# Power.net
KiCad netlist of a schematic drawn in Altium Designer
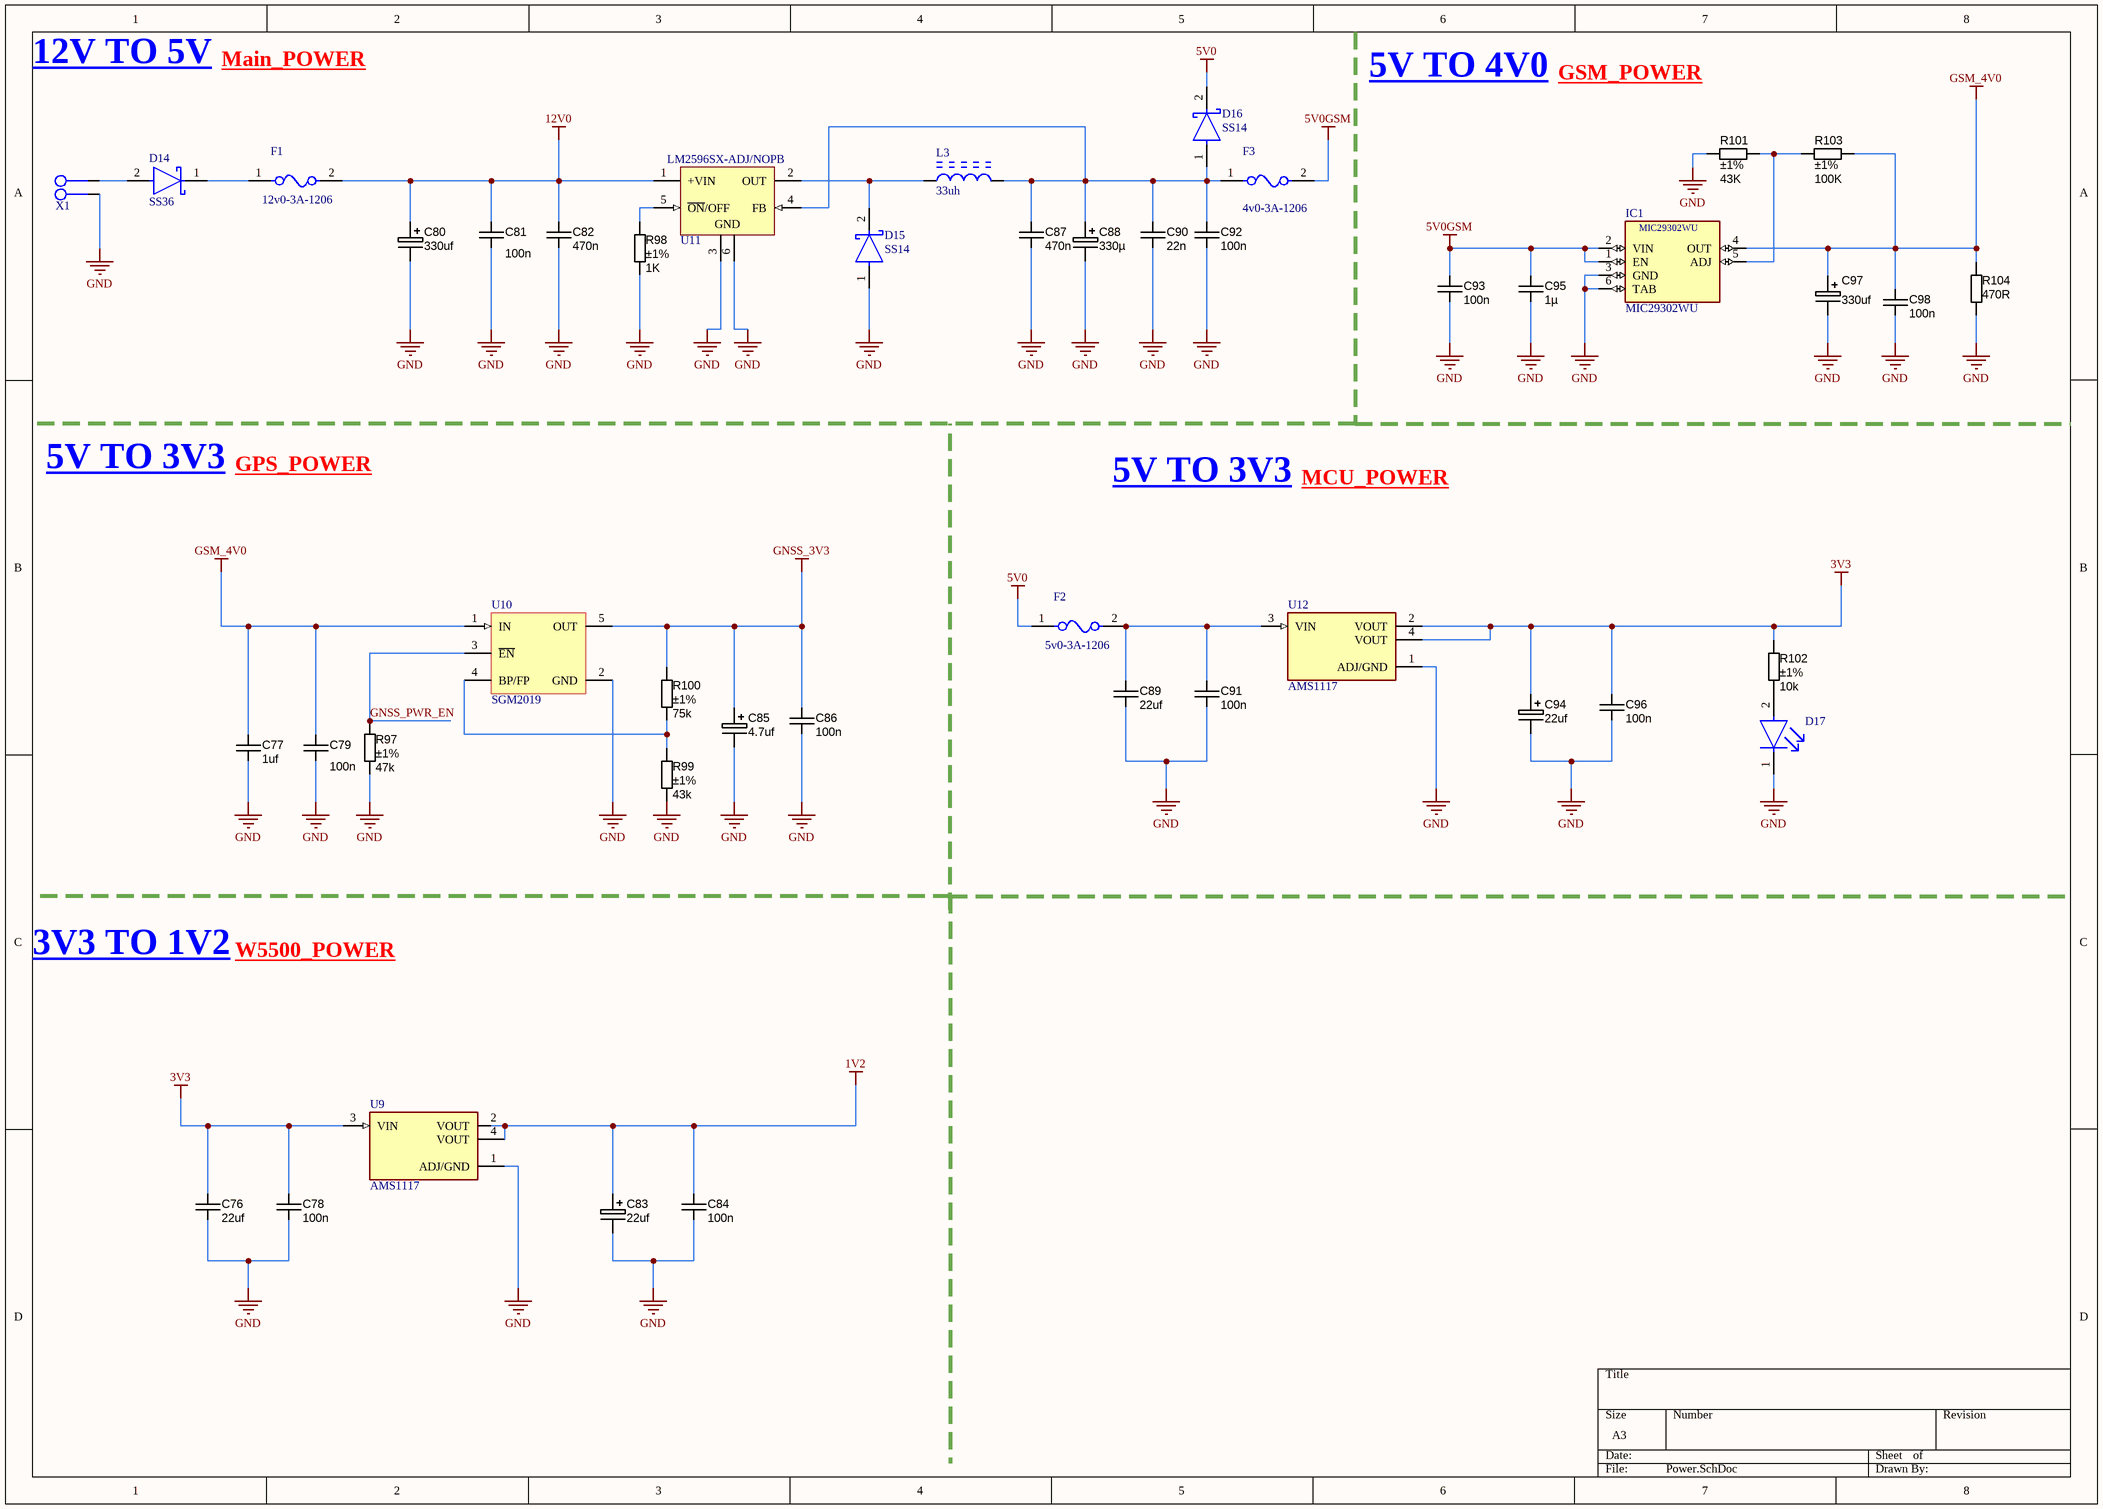
[diagram p0: Power.SchDoc]

(export (version "E")
  (design (tool "Eeschema 10.0.6"))
  (components
    (comp (ref "C76")
      (value "22uf")
      (footprint "CAPC1608X90N")
      (description "Capacitor SMD Cer 22uf 10% 16V X7R 0603")
      (fields (field (name "TOLERANCE") "±10%"))
      (libsource (lib "PBL - Capacitors") (part "CAPC_470n_0603_X7R_16V_10%"))
    )
    (comp (ref "C77")
      (value "1uf")
      (footprint "CAPC1608X90N")
      (description "Capacitor SMD Cer 1uf 10% 16V X7R 0603")
      (fields (field (name "TOLERANCE") "±10%"))
      (libsource (lib "PBL - Capacitors") (part "CAPC_470n_0603_X7R_16V_10%"))
    )
    (comp (ref "C78")
      (value "100n")
      (footprint "CAPC1608X90N")
      (description "Capacitor SMD Cer 100nF 10% 50V X7R 0603")
      (fields (field (name "TOLERANCE") "±10%") (field (name "Comment") "approved sub OK"))
      (libsource (lib "PBL - Capacitors") (part "CAPC_100n_0603_X7R_50V_10%"))
    )
    (comp (ref "C79")
      (value "100n")
      (footprint "CAPC1608X90N")
      (description "Capacitor SMD Cer 100nF 10% 16V X7R 0603")
      (fields (field (name "TOLERANCE") "±10%"))
      (libsource (lib "PBL - Capacitors") (part "CAPC_470n_0603_X7R_16V_10%"))
    )
    (comp (ref "C80")
      (value "330uf")
      (footprint "C_EL_8")
      (description "Capacitor SMD Tant 330uF 20% 6V3 2917")
      (fields
        (field (name "TOLERANCE") "±20%")
        (field (name "MANUFACTURER PART NUMBER") "T520D337M006ATE015")
      )
      (libsource (lib "PBL - Capacitors") (part "CAPT_330u_2917_6V3"))
    )
    (comp (ref "C81")
      (value "100n")
      (footprint "CAPC1608X90N")
      (description "Capacitor SMD Cer 100nF 10% 16V X7R 0603")
      (fields (field (name "TOLERANCE") "±10%"))
      (libsource (lib "PBL - Capacitors") (part "CAPC_470n_0603_X7R_16V_10%"))
    )
    (comp (ref "C82")
      (value "470n")
      (footprint "CAPC3216X180N")
      (description "Capacitor SMD Cer 470nF 10% 10V X5R 1206")
      (fields (field (name "TOLERANCE") "±10%") (field (name "Comment") "approved sub OK"))
      (libsource (lib "PBL - Capacitors") (part "CAPC_10u_1206_10V"))
    )
    (comp (ref "C83")
      (value "22uf")
      (footprint "C_TN_3216")
      (description "Capacitor SMD Tant 22uF 20% 6V3 2917")
      (fields
        (field (name "TOLERANCE") "±20%")
        (field (name "MANUFACTURER PART NUMBER") "T520D337M006ATE015")
      )
      (libsource (lib "PBL - Capacitors") (part "CAPT_330u_2917_6V3"))
    )
    (comp (ref "C84")
      (value "100n")
      (footprint "CAPC1608X90N")
      (description "Capacitor SMD Cer 100nF 10% 50V X7R 0603")
      (fields (field (name "TOLERANCE") "±10%") (field (name "Comment") "approved sub OK"))
      (libsource (lib "PBL - Capacitors") (part "CAPC_100n_0603_X7R_50V_10%"))
    )
    (comp (ref "C85")
      (value "4.7uf")
      (footprint "C_TN_3216")
      (description "Capacitor SMD Tant 4.7uF 20% 6V3 2917")
      (fields
        (field (name "TOLERANCE") "±20%")
        (field (name "MANUFACTURER PART NUMBER") "T520D337M006ATE015")
      )
      (libsource (lib "PBL - Capacitors") (part "CAPT_330u_2917_6V3"))
    )
    (comp (ref "C86")
      (value "100n")
      (footprint "CAPC1608X90N")
      (description "Capacitor SMD Cer 100nF 10% 50V X7R 0603")
      (fields (field (name "TOLERANCE") "±10%") (field (name "Comment") "approved sub OK"))
      (libsource (lib "PBL - Capacitors") (part "CAPC_100n_0603_X7R_50V_10%"))
    )
    (comp (ref "C87")
      (value "470n")
      (footprint "CAPC3216X180N")
      (description "Capacitor SMD Cer 470nF 10% 10V X5R 1206")
      (fields (field (name "TOLERANCE") "±10%") (field (name "Comment") "approved sub OK"))
      (libsource (lib "PBL - Capacitors") (part "CAPC_10u_1206_10V"))
    )
    (comp (ref "C88")
      (value "330µ")
      (footprint "C_TN_7343")
      (description "Capacitor SMD Tant 330uF 20% 6V3 2917")
      (fields
        (field (name "TOLERANCE") "±20%")
        (field (name "MANUFACTURER PART NUMBER") "T520D337M006ATE015")
      )
      (libsource (lib "PBL - Capacitors") (part "CAPT_330u_2917_6V3"))
    )
    (comp (ref "C89")
      (value "22uf")
      (footprint "CAPC1608X90N")
      (description "Capacitor SMD Cer 22uf 10% 16V X7R 0603")
      (fields (field (name "TOLERANCE") "±10%"))
      (libsource (lib "PBL - Capacitors") (part "CAPC_470n_0603_X7R_16V_10%"))
    )
    (comp (ref "C90")
      (value "22n")
      (footprint "CAPC1608X90N")
      (description "Capacitor SMD Cer 22nF 10% 16V X7R 0603")
      (fields (field (name "TOLERANCE") "±10%"))
      (libsource (lib "PBL - Capacitors") (part "CAPC_470n_0603_X7R_16V_10%"))
    )
    (comp (ref "C91")
      (value "100n")
      (footprint "CAPC1608X90N")
      (description "Capacitor SMD Cer 100nF 10% 50V X7R 0603")
      (fields (field (name "TOLERANCE") "±10%") (field (name "Comment") "approved sub OK"))
      (libsource (lib "PBL - Capacitors") (part "CAPC_100n_0603_X7R_50V_10%"))
    )
    (comp (ref "C92")
      (value "100n")
      (footprint "CAPC1608X90N")
      (description "Capacitor SMD Cer 100nF 10% 16V X7R 0603")
      (fields (field (name "TOLERANCE") "±10%"))
      (libsource (lib "PBL - Capacitors") (part "CAPC_470n_0603_X7R_16V_10%"))
    )
    (comp (ref "C93")
      (value "100n")
      (footprint "CAPC1608X90N")
      (description "Capacitor SMD Cer 100nF 10% 50V X7R 0603")
      (fields (field (name "TOLERANCE") "±10%") (field (name "Comment") "approved sub OK"))
      (libsource (lib "PBL - Capacitors") (part "CAPC_100n_0603_X7R_50V_10%"))
    )
    (comp (ref "C94")
      (value "22uf")
      (footprint "C_TN_3216")
      (description "Capacitor SMD Tant 22uF 20% 6V3 2917")
      (fields
        (field (name "TOLERANCE") "±20%")
        (field (name "MANUFACTURER PART NUMBER") "T520D337M006ATE015")
      )
      (libsource (lib "PBL - Capacitors") (part "CAPT_330u_2917_6V3"))
    )
    (comp (ref "C95")
      (value "1µ")
      (footprint "CAPC3216X180N")
      (description "Capacitor SMD Cer 1uF 10% 10V X5R 1206")
      (fields (field (name "TOLERANCE") "±10%") (field (name "Comment") "approved sub OK"))
      (libsource (lib "PBL - Capacitors") (part "CAPC_10u_1206_10V"))
    )
    (comp (ref "C96")
      (value "100n")
      (footprint "CAPC1608X90N")
      (description "Capacitor SMD Cer 100nF 10% 50V X7R 0603")
      (fields (field (name "TOLERANCE") "±10%") (field (name "Comment") "approved sub OK"))
      (libsource (lib "PBL - Capacitors") (part "CAPC_100n_0603_X7R_50V_10%"))
    )
    (comp (ref "C97")
      (value "330uf")
      (footprint "C_EL_8")
      (description "Capacitor SMD Tant 330uF 20% 6V3 2917")
      (fields
        (field (name "TOLERANCE") "±20%")
        (field (name "MANUFACTURER PART NUMBER") "T520D337M006ATE015")
      )
      (libsource (lib "PBL - Capacitors") (part "CAPT_330u_2917_6V3"))
    )
    (comp (ref "C98")
      (value "100n")
      (footprint "CAPC1608X90N")
      (description "Capacitor SMD Cer 100nF 10% 50V X7R 0603")
      (fields (field (name "TOLERANCE") "±10%") (field (name "Comment") "approved sub OK"))
      (libsource (lib "PBL - Capacitors") (part "CAPC_100n_0603_X7R_50V_10%"))
    )
    (comp (ref "D14")
      (value "SS36")
      (footprint "FP-403AG-MFG")
      (description "DIODE SCHOTTKY 60V 3A SMC")
      (fields
        (field (name "MANUFACTURER") "ON Semiconductor")
        (field (name "OCTOPART") "https://octopart.com/ss36-on+semiconductor-84331627")
      )
      (libsource (lib "Altium Content Vault") (part "1d6ec82d83fb6aee721767c19dac4b9"))
    )
    (comp (ref "D15")
      (value "SS14")
      (footprint "FP-403AE-MFG")
      (description "DIODE SCHOTTKY 40V 1A SMA")
      (fields
        (field (name "MANUFACTURER") "ON Semiconductor")
        (field (name "OCTOPART") "https://octopart.com/ss14-on+semiconductor-29205033")
      )
      (libsource (lib "Altium Content Vault") (part "360ad2f4ac25a952324d13796385471"))
    )
    (comp (ref "D16")
      (value "SS14")
      (footprint "FP-403AE-MFG")
      (description "DIODE SCHOTTKY 40V 1A SMA")
      (fields
        (field (name "MANUFACTURER") "ON Semiconductor")
        (field (name "OCTOPART") "https://octopart.com/ss14-on+semiconductor-29205033")
      )
      (libsource (lib "Altium Content Vault") (part "360ad2f4ac25a952324d13796385471"))
    )
    (comp (ref "D17")
      (value "LTST-C191TBKT")
      (footprint "FP-LTST-C191TBKT-MFG")
      (description "LED BLUE CLEAR CHIP SMD")
      (libsource (lib "Altium Content Vault") (part "8706943c75ba83719d021d2fdc84c58"))
    )
    (comp (ref "F1")
      (value "12v0-3A-1206")
      (footprint "FP-nanoSMDC-MFG")
      (description "PTC RESET FUSE 48V 120MA 1206")
      (fields
        (field (name "MANUFACTURER") "Littelfuse")
        (field (name "MANUFACTURER PART NUMBER") "NANOSMDC012F-2")
      )
      (libsource (lib "Altium Content Vault") (part "5bcf9b9f640e542cf0359d10258e979"))
    )
    (comp (ref "F2")
      (value "5v0-3A-1206")
      (footprint "FP-nanoSMDC-MFG")
      (description "PTC RESET FUSE 48V 120MA 1206")
      (fields
        (field (name "MANUFACTURER") "Littelfuse")
        (field (name "MANUFACTURER PART NUMBER") "NANOSMDC012F-2")
      )
      (libsource (lib "Altium Content Vault") (part "5bcf9b9f640e542cf0359d10258e979"))
    )
    (comp (ref "F3")
      (value "4v0-3A-1206")
      (footprint "FP-nanoSMDC-MFG")
      (description "PTC RESET FUSE 48V 120MA 1206")
      (fields
        (field (name "MANUFACTURER") "Littelfuse")
        (field (name "MANUFACTURER PART NUMBER") "NANOSMDC012F-2")
      )
      (libsource (lib "Altium Content Vault") (part "5bcf9b9f640e542cf0359d10258e979"))
    )
    (comp (ref "IC1")
      (value "MIC29302WU")
      (footprint "TO263-5")
      (description "Linear Voltage Regulator IC 1 Output 3A TO-263-5")
      (fields (field (name "MF") "Microchip Technology"))
      (libsource (lib "MIC29302WU") (part "MIC29302WU"))
    )
    (comp (ref "L3")
      (value "33uh")
      (footprint "BOUR-SRR1280-2_V")
      (description "Shielded SMD Power Inductor, 33 uH, +/- 20%, -40 to 125 degC, 2-Pin SMD, RoHS, Tape and Reel")
      (fields (field (name "MANUFACTURER") "Bourns") (field (name "PARTNUMBER") "SRR1280"))
      (libsource (lib "Altium Content Vault") (part "IND-FERR-2"))
    )
    (comp (ref "R97")
      (value "47k")
      (footprint "RESC1608X55N")
      (description "Resistor SMD chip 47k Ohm 0.1W 1% 0603")
      (fields (field (name "TOLERANCE") "±1%") (field (name "Comment") "Thick Film"))
      (libsource (lib "") (part "RES_1K_0603_1%_1"))
    )
    (comp (ref "R98")
      (value "1K")
      (footprint "RESC1608X55N")
      (description "Resistor SMD chip 1k Ohm 0.1W 1% 0603")
      (fields (field (name "TOLERANCE") "±1%") (field (name "Comment") "Thick Film"))
      (libsource (lib "") (part "RES_1K_0603_1%_1"))
    )
    (comp (ref "R99")
      (value "43k")
      (footprint "RESC1608X55N")
      (description "Resistor SMD chip 43k Ohm 0.1W 1% 0603")
      (fields (field (name "TOLERANCE") "±1%") (field (name "Comment") "Thick Film"))
      (libsource (lib "") (part "RES_1K_0603_1%_1"))
    )
    (comp (ref "R100")
      (value "75k")
      (footprint "RESC1608X55N")
      (description "Resistor SMD chip 75k Ohm 0.1W 1% 0603")
      (fields (field (name "TOLERANCE") "±1%") (field (name "Comment") "Thick Film"))
      (libsource (lib "") (part "RES_1K_0603_1%_1"))
    )
    (comp (ref "R101")
      (value "43K")
      (footprint "RESC1608X55N")
      (description "Resistor SMD chip 43k Ohm 0.1W 1% 0603")
      (fields (field (name "TOLERANCE") "±1%") (field (name "Comment") "Thick Film"))
      (libsource (lib "PBL - Resistors") (part "RES_1K_0603_1%"))
    )
    (comp (ref "R102")
      (value "10k")
      (footprint "RESC1608X55N")
      (description "Resistor SMD chip 10k Ohm 0.1W 1% 0603")
      (fields (field (name "TOLERANCE") "±1%") (field (name "Comment") "Thick Film"))
      (libsource (lib "") (part "RES_1K_0603_1%_1"))
    )
    (comp (ref "R103")
      (value "100K")
      (footprint "RESC1608X55N")
      (description "Resistor SMD chip 100k Ohm 0.1W 1% 0603")
      (fields (field (name "TOLERANCE") "±1%") (field (name "Comment") "Thick Film"))
      (libsource (lib "PBL - Resistors") (part "RES_1K_0603_1%"))
    )
    (comp (ref "R104")
      (value "470R")
      (footprint "RESC3216X70N")
      (description "Resistor SMD chip 470 Ohm 0.25W 5% 1206")
      (fields (field (name "TOLERANCE") "±5%") (field (name "Comment") "Thick Film"))
      (libsource (lib "PBL - Resistors") (part "RES_10R_1206_5%"))
    )
    (comp (ref "U9")
      (value "AMS1117")
      (footprint "SOT223")
      (description "UNO PLUS Arduino R3 Shield, Xbee Arduino IDE Wheeled Robotics Kit")
      (fields (field (name "MF") "Seeed Technology"))
      (libsource (lib "AMS1117") (part "AMS1117"))
    )
    (comp (ref "U10")
      (value "SGM2019")
      (footprint "SOT95P280X100-5N")
      (description "SGM2019 Regulator \r\nLow Power, Low Dropout,\r\nRF-Linear Regulators\r\n\r\nTSOT-23 T/R")
      (fields
        (field (name "MP") "LT1761ES5-5#TRPBF")
        (field (name "DIGI-KEY_PART_NUMBER") "LT1761ES5-5#TRPBFCT-ND")
      )
      (libsource (lib "SGM2019") (part "SGM2019"))
    )
    (comp (ref "U11")
      (value "LM2596SX-ADJ/NOPB")
      (footprint "KTT0005B_L")
      (fields (field (name "PARTNUMBER") "LM2596") (field (name "MANUFACTURER") "Texas Instruments"))
      (libsource (lib "Altium Content Vault") (part "TI-LM2596-TO-263-5"))
    )
    (comp (ref "U12")
      (value "AMS1117")
      (footprint "SOT223")
      (description "UNO PLUS Arduino R3 Shield, Xbee Arduino IDE Wheeled Robotics Kit")
      (fields (field (name "MF") "Seeed Technology"))
      (libsource (lib "AMS1117") (part "AMS1117"))
    )
    (comp (ref "X1")
      (value "Phoenix MKDSN 02")
      (footprint "PRKR2A")
      (libsource (lib "Connector") (part "Phoenix MKDSN 02"))
    )
  )
  (nets
    (net (code "1") (name "/GNSS_PWR_EN") (class "Default")
      (node (ref "R97") (pin "1") (pinfunction "1_1") (pintype "passive"))
      (node (ref "U10") (pin "3") (pinfunction "~{EN}_3") (pintype "passive"))
    )
    (net (code "2") (name "1V2") (class "Default")
      (node (ref "C83") (pin "1") (pintype "passive"))
      (node (ref "C84") (pin "1") (pintype "passive"))
      (node (ref "U9") (pin "2") (pinfunction "VOUT_2") (pintype "power_in"))
      (node (ref "U9") (pin "4") (pinfunction "VOUT_4") (pintype "power_in"))
    )
    (net (code "3") (name "3V3") (class "Default")
      (node (ref "C76") (pin "1") (pintype "passive"))
      (node (ref "C78") (pin "1") (pintype "passive"))
      (node (ref "C94") (pin "1") (pintype "passive"))
      (node (ref "C96") (pin "1") (pintype "passive"))
      (node (ref "R102") (pin "1") (pinfunction "1_1") (pintype "passive"))
      (node (ref "U12") (pin "2") (pinfunction "VOUT_2") (pintype "power_in"))
      (node (ref "U12") (pin "4") (pinfunction "VOUT_4") (pintype "power_in"))
      (node (ref "U9") (pin "3") (pinfunction "VIN_3") (pintype "input"))
    )
    (net (code "4") (name "5V0") (class "Default")
      (node (ref "D16") (pin "2") (pinfunction "C_2") (pintype "passive"))
      (node (ref "F2") (pin "1") (pinfunction "1_1") (pintype "passive"))
    )
    (net (code "5") (name "5V0GSM") (class "Default")
      (node (ref "C93") (pin "1") (pintype "passive"))
      (node (ref "C95") (pin "1") (pintype "passive"))
      (node (ref "F3") (pin "2") (pinfunction "2_2") (pintype "passive"))
      (node (ref "IC1") (pin "1") (pinfunction "EN_1") (pintype "bidirectional"))
      (node (ref "IC1") (pin "2") (pinfunction "VIN_2") (pintype "bidirectional"))
    )
    (net (code "6") (name "12V0") (class "Default")
      (node (ref "C80") (pin "1") (pintype "passive"))
      (node (ref "C81") (pin "1") (pintype "passive"))
      (node (ref "C82") (pin "1") (pintype "passive"))
      (node (ref "F1") (pin "2") (pinfunction "2_2") (pintype "passive"))
      (node (ref "U11") (pin "1") (pinfunction "+VIN_1") (pintype "power_in"))
    )
    (net (code "7") (name "GND") (class "Default")
      (node (ref "C76") (pin "2") (pintype "passive"))
      (node (ref "C77") (pin "2") (pintype "passive"))
      (node (ref "C78") (pin "2") (pintype "passive"))
      (node (ref "C79") (pin "2") (pintype "passive"))
      (node (ref "C80") (pin "2") (pintype "passive"))
      (node (ref "C81") (pin "2") (pintype "passive"))
      (node (ref "C82") (pin "2") (pintype "passive"))
      (node (ref "C83") (pin "2") (pintype "passive"))
      (node (ref "C84") (pin "2") (pintype "passive"))
      (node (ref "C85") (pin "2") (pintype "passive"))
      (node (ref "C86") (pin "2") (pintype "passive"))
      (node (ref "C87") (pin "2") (pintype "passive"))
      (node (ref "C88") (pin "2") (pintype "passive"))
      (node (ref "C89") (pin "2") (pintype "passive"))
      (node (ref "C90") (pin "2") (pintype "passive"))
      (node (ref "C91") (pin "2") (pintype "passive"))
      (node (ref "C92") (pin "2") (pintype "passive"))
      (node (ref "C93") (pin "2") (pintype "passive"))
      (node (ref "C94") (pin "2") (pintype "passive"))
      (node (ref "C95") (pin "2") (pintype "passive"))
      (node (ref "C96") (pin "2") (pintype "passive"))
      (node (ref "C97") (pin "2") (pintype "passive"))
      (node (ref "C98") (pin "2") (pintype "passive"))
      (node (ref "D15") (pin "1") (pinfunction "A_1") (pintype "passive"))
      (node (ref "D17") (pin "1") (pinfunction "C_1") (pintype "passive"))
      (node (ref "IC1") (pin "3") (pinfunction "GND_3") (pintype "bidirectional"))
      (node (ref "IC1") (pin "6") (pinfunction "TAB_6") (pintype "bidirectional"))
      (node (ref "R101") (pin "1") (pinfunction "1_1") (pintype "passive"))
      (node (ref "R104") (pin "2") (pinfunction "2_2") (pintype "passive"))
      (node (ref "R97") (pin "2") (pinfunction "2_2") (pintype "passive"))
      (node (ref "R98") (pin "2") (pinfunction "2_2") (pintype "passive"))
      (node (ref "R99") (pin "2") (pinfunction "2_2") (pintype "passive"))
      (node (ref "U10") (pin "2") (pinfunction "GND_2") (pintype "power_in"))
      (node (ref "U11") (pin "3") (pinfunction "GND_3") (pintype "power_in"))
      (node (ref "U11") (pin "6") (pinfunction "GND_6") (pintype "power_in"))
      (node (ref "U12") (pin "1") (pinfunction "ADJ/GND_1") (pintype "power_in"))
      (node (ref "U9") (pin "1") (pinfunction "ADJ/GND_1") (pintype "power_in"))
      (node (ref "X1") (pin "1") (pinfunction "1_1") (pintype "passive"))
    )
    (net (code "8") (name "GNSS_3V3") (class "Default")
      (node (ref "C85") (pin "1") (pintype "passive"))
      (node (ref "C86") (pin "1") (pintype "passive"))
      (node (ref "R100") (pin "1") (pinfunction "1_1") (pintype "passive"))
      (node (ref "U10") (pin "5") (pinfunction "OUT_5") (pintype "power_in"))
    )
    (net (code "9") (name "GSM_4V0") (class "Default")
      (node (ref "C77") (pin "1") (pintype "passive"))
      (node (ref "C79") (pin "1") (pintype "passive"))
      (node (ref "C97") (pin "1") (pintype "passive"))
      (node (ref "C98") (pin "1") (pintype "passive"))
      (node (ref "IC1") (pin "4") (pinfunction "OUT_4") (pintype "bidirectional"))
      (node (ref "R103") (pin "2") (pinfunction "2_2") (pintype "passive"))
      (node (ref "R104") (pin "1") (pinfunction "1_1") (pintype "passive"))
      (node (ref "U10") (pin "1") (pinfunction "IN_1") (pintype "input"))
    )
    (net (code "10") (name "Net-(D14-A)") (class "Default")
      (node (ref "D14") (pin "2") (pinfunction "A_2") (pintype "passive"))
      (node (ref "X1") (pin "2") (pinfunction "2_2") (pintype "passive"))
    )
    (net (code "11") (name "Net-(D14-C)") (class "Default")
      (node (ref "D14") (pin "1") (pinfunction "C_1") (pintype "passive"))
      (node (ref "F1") (pin "1") (pinfunction "1_1") (pintype "passive"))
    )
    (net (code "12") (name "Net-(D15-C)") (class "Default")
      (node (ref "D15") (pin "2") (pinfunction "C_2") (pintype "passive"))
      (node (ref "L3") (pin "1") (pinfunction "1_1") (pintype "passive"))
      (node (ref "U11") (pin "2") (pinfunction "OUT_2") (pintype "power_in"))
    )
    (net (code "13") (name "Net-(D16-A)") (class "Default")
      (node (ref "C87") (pin "1") (pintype "passive"))
      (node (ref "C88") (pin "1") (pintype "passive"))
      (node (ref "C90") (pin "1") (pintype "passive"))
      (node (ref "C92") (pin "1") (pintype "passive"))
      (node (ref "D16") (pin "1") (pinfunction "A_1") (pintype "passive"))
      (node (ref "F3") (pin "1") (pinfunction "1_1") (pintype "passive"))
      (node (ref "L3") (pin "2") (pinfunction "2_2") (pintype "passive"))
      (node (ref "U11") (pin "4") (pinfunction "FB_4") (pintype "input"))
    )
    (net (code "14") (name "Net-(D17-A)") (class "Default")
      (node (ref "D17") (pin "2") (pinfunction "A_2") (pintype "passive"))
      (node (ref "R102") (pin "2") (pinfunction "2_2") (pintype "passive"))
    )
    (net (code "15") (name "Net-(IC1-ADJ)") (class "Default")
      (node (ref "IC1") (pin "5") (pinfunction "ADJ_5") (pintype "bidirectional"))
      (node (ref "R101") (pin "2") (pinfunction "2_2") (pintype "passive"))
      (node (ref "R103") (pin "1") (pinfunction "1_1") (pintype "passive"))
    )
    (net (code "16") (name "Net-(U10-BP{slash}FP)") (class "Default")
      (node (ref "R100") (pin "2") (pinfunction "2_2") (pintype "passive"))
      (node (ref "R99") (pin "1") (pinfunction "1_1") (pintype "passive"))
      (node (ref "U10") (pin "4") (pinfunction "BP/FP_4") (pintype "passive"))
    )
    (net (code "17") (name "Net-(U11-~{ON}{slash}OFF)") (class "Default")
      (node (ref "R98") (pin "1") (pinfunction "1_1") (pintype "passive"))
      (node (ref "U11") (pin "5") (pinfunction "~{ON}/OFF_5") (pintype "input"))
    )
    (net (code "18") (name "Net-(U12-VIN)") (class "Default")
      (node (ref "C89") (pin "1") (pintype "passive"))
      (node (ref "C91") (pin "1") (pintype "passive"))
      (node (ref "F2") (pin "2") (pinfunction "2_2") (pintype "passive"))
      (node (ref "U12") (pin "3") (pinfunction "VIN_3") (pintype "input"))
    )
  )
)
